# LoRa_Sensor.net
KiCad netlist of a schematic drawn in EAGLE
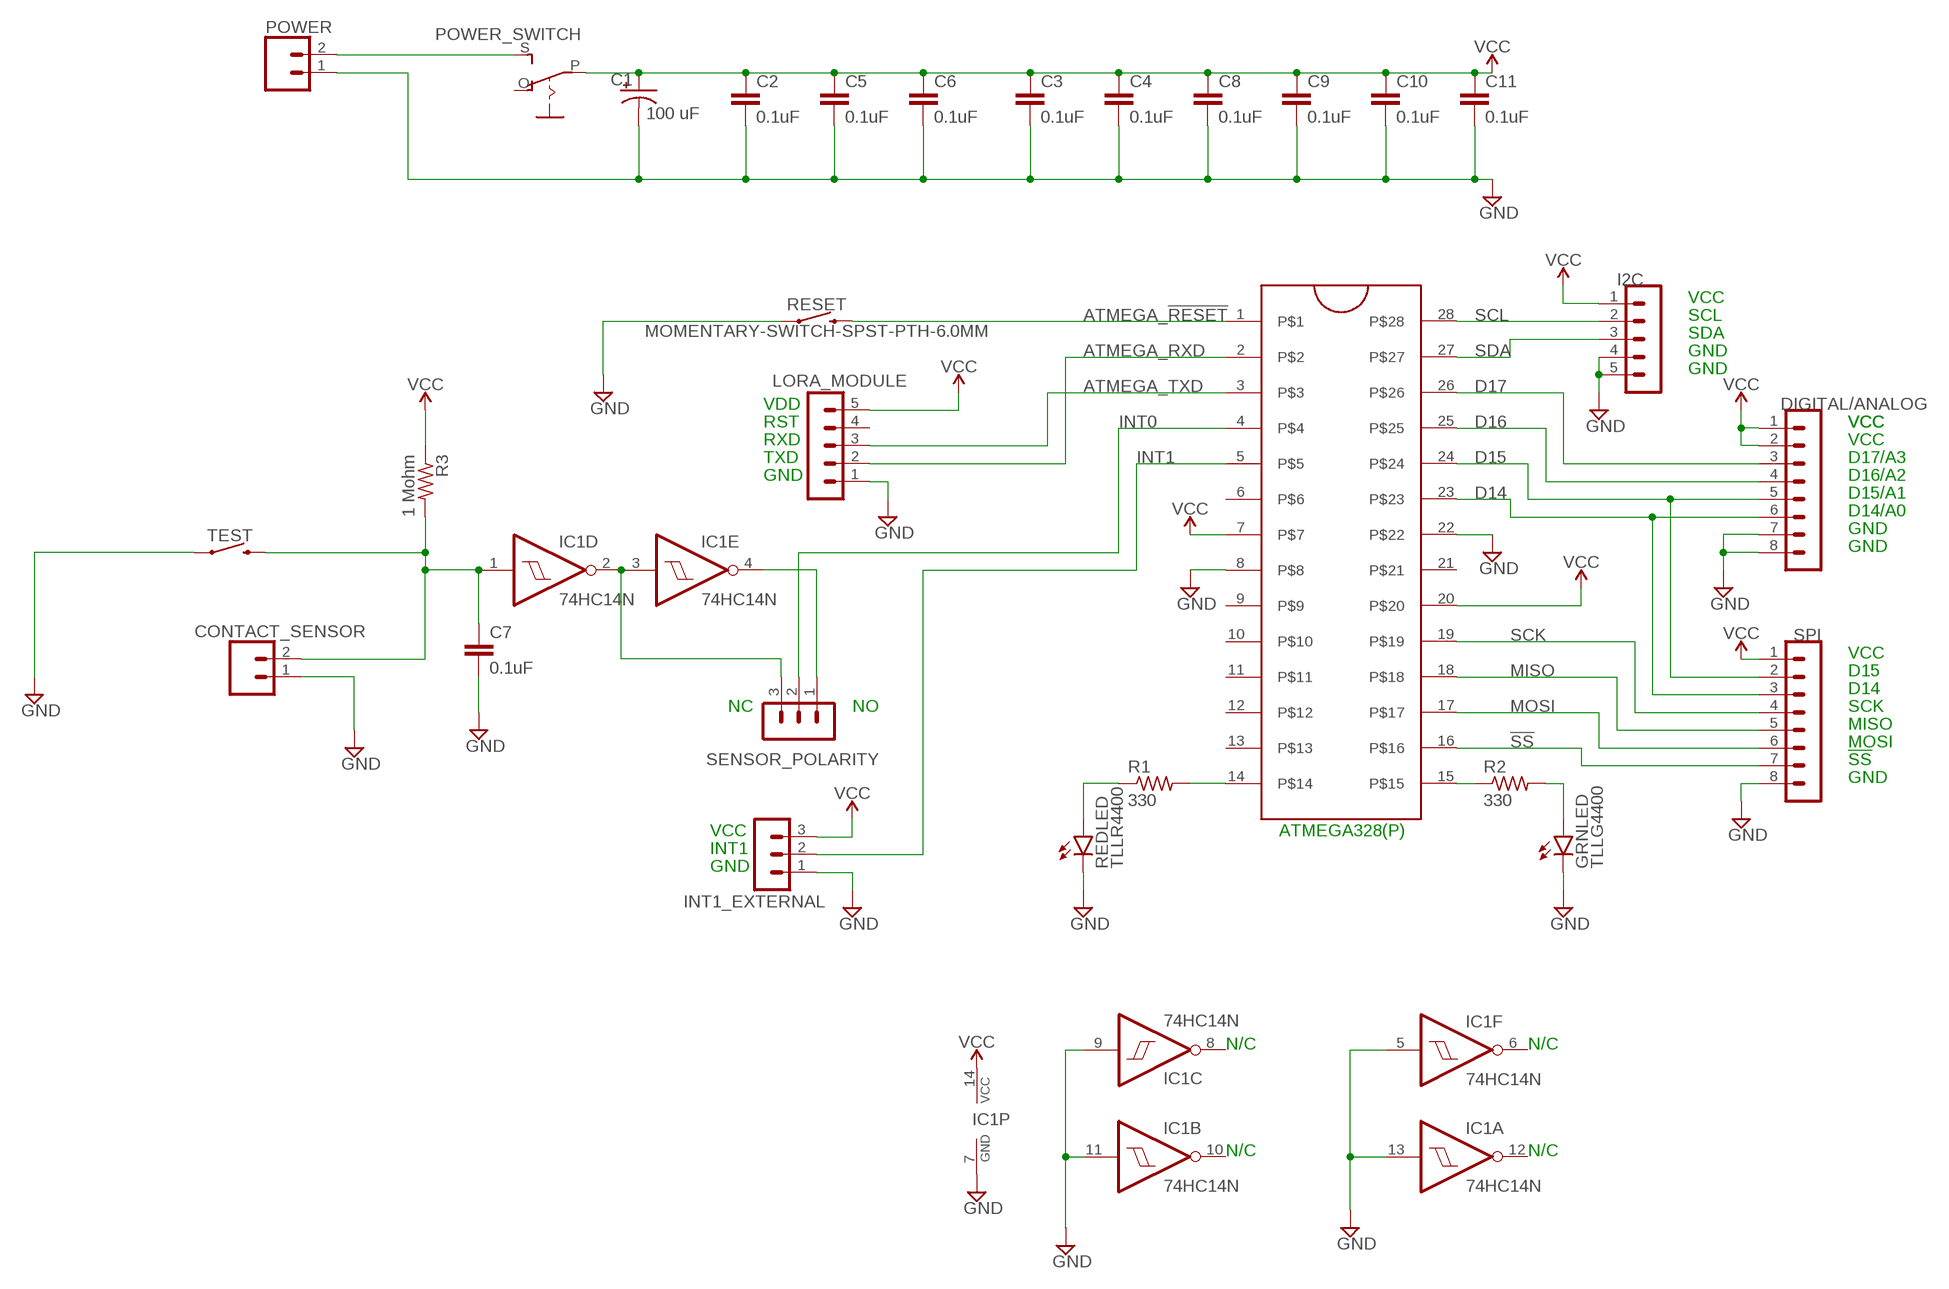
[diagram p0: schematic, sheet 1]

(export (version "E")
  (design (tool "Eeschema 10.0.6"))
  (components
    (comp (ref "C1")
      (value "100 uF")
      (footprint "eagle-import:E2,5-6")
      (libsource (lib "eagle-import") (part "CPOL-USE2.5-6"))
    )
    (comp (ref "C2")
      (value "0.1uF")
      (footprint "eagle-import:CAP-PTH-SMALL-KIT")
      (libsource (lib "eagle-import") (part "0.1UF-KIT-EZ-50V-20%"))
    )
    (comp (ref "C3")
      (value "0.1uF")
      (footprint "eagle-import:CAP-PTH-SMALL-KIT")
      (libsource (lib "eagle-import") (part "0.1UF-KIT-EZ-50V-20%"))
    )
    (comp (ref "C4")
      (value "0.1uF")
      (footprint "eagle-import:CAP-PTH-SMALL-KIT")
      (libsource (lib "eagle-import") (part "0.1UF-KIT-EZ-50V-20%"))
    )
    (comp (ref "C5")
      (value "0.1uF")
      (footprint "eagle-import:CAP-PTH-SMALL-KIT")
      (libsource (lib "eagle-import") (part "0.1UF-KIT-EZ-50V-20%"))
    )
    (comp (ref "C6")
      (value "0.1uF")
      (footprint "eagle-import:CAP-PTH-SMALL-KIT")
      (libsource (lib "eagle-import") (part "0.1UF-KIT-EZ-50V-20%"))
    )
    (comp (ref "C7")
      (value "0.1uF")
      (footprint "eagle-import:CAP-PTH-SMALL-KIT")
      (libsource (lib "eagle-import") (part "0.1UF-KIT-EZ-50V-20%"))
    )
    (comp (ref "C8")
      (value "0.1uF")
      (footprint "eagle-import:CAP-PTH-SMALL-KIT")
      (libsource (lib "eagle-import") (part "0.1UF-KIT-EZ-50V-20%"))
    )
    (comp (ref "C9")
      (value "0.1uF")
      (footprint "eagle-import:CAP-PTH-SMALL-KIT")
      (libsource (lib "eagle-import") (part "0.1UF-KIT-EZ-50V-20%"))
    )
    (comp (ref "C10")
      (value "0.1uF")
      (footprint "eagle-import:CAP-PTH-SMALL-KIT")
      (libsource (lib "eagle-import") (part "0.1UF-KIT-EZ-50V-20%"))
    )
    (comp (ref "C11")
      (value "0.1uF")
      (footprint "eagle-import:CAP-PTH-SMALL-KIT")
      (libsource (lib "eagle-import") (part "0.1UF-KIT-EZ-50V-20%"))
    )
    (comp (ref "CONTACT_SENSOR")
      (value "CONN_023.5MM")
      (footprint "eagle-import:SCREWTERMINAL-3.5MM-2")
      (libsource (lib "eagle-import") (part "CONN_023.5MM"))
    )
    (comp (ref "DIGITAL/ANALOG")
      (value "MA08-1")
      (footprint "eagle-import:MA08-1")
      (libsource (lib "eagle-import") (part "MA08-1"))
    )
    (comp (ref "GRNLED")
      (value "TLLG4400")
      (footprint "eagle-import:LED3MM")
      (fields (field (name "MF") "VISHAY SEMICONDUCTOR"))
      (libsource (lib "eagle-import") (part "TLLG4400"))
    )
    (comp (ref "I2C")
      (value "MA05-1")
      (footprint "eagle-import:MA05-1")
      (libsource (lib "eagle-import") (part "MA05-1"))
    )
    (comp (ref "IC1")
      (value "74HC14N")
      (footprint "eagle-import:DIL14")
      (libsource (lib "eagle-import") (part "7414NHC"))
    )
    (comp (ref "INT1_EXTERNAL")
      (value "MA03-1")
      (footprint "eagle-import:MA03-1")
      (libsource (lib "eagle-import") (part "MA03-1"))
    )
    (comp (ref "J1")
      (value "ZIFSOCKET-28-3\"")
      (footprint "eagle-import:DIL28-3-ZIF_SOCKET")
      (libsource (lib "eagle-import") (part "ZIFSOCKET-28-3{dblquote}"))
    )
    (comp (ref "LORA_MODULE")
      (value "MA05-1")
      (footprint "eagle-import:MA05-1")
      (libsource (lib "eagle-import") (part "MA05-1"))
    )
    (comp (ref "POWER")
      (value "CONN_023.5MM")
      (footprint "eagle-import:SCREWTERMINAL-3.5MM-2")
      (libsource (lib "eagle-import") (part "CONN_023.5MM"))
    )
    (comp (ref "POWER_SWITCH")
      (value "EG1218S")
      (footprint "eagle-import:EG1218")
      (libsource (lib "eagle-import") (part "EG1218S"))
    )
    (comp (ref "R1")
      (value "330")
      (footprint "eagle-import:0309_12")
      (libsource (lib "eagle-import") (part "R-US_0309/12"))
    )
    (comp (ref "R2")
      (value "330")
      (footprint "eagle-import:0309_12")
      (libsource (lib "eagle-import") (part "R-US_0309/12"))
    )
    (comp (ref "R3")
      (value "1 Mohm")
      (footprint "eagle-import:0309_12")
      (libsource (lib "eagle-import") (part "R-US_0309/12"))
    )
    (comp (ref "REDLED")
      (value "TLLR4400")
      (footprint "eagle-import:LED3MM")
      (fields (field (name "MF") "VISHAY SEMICONDUCTOR"))
      (libsource (lib "eagle-import") (part "TLLR4400"))
    )
    (comp (ref "RESET")
      (value "MOMENTARY-SWITCH-SPST-PTH-6.0MM")
      (footprint "eagle-import:TACTILE_SWITCH_PTH_6.0MM")
      (libsource (lib "eagle-import") (part "MOMENTARY-SWITCH-SPST-PTH-6.0MM"))
    )
    (comp (ref "SENSOR_POLARITY")
      (value "MA03-1")
      (footprint "eagle-import:MA03-1")
      (libsource (lib "eagle-import") (part "MA03-1"))
    )
    (comp (ref "SPI")
      (value "MA08-1")
      (footprint "eagle-import:MA08-1")
      (libsource (lib "eagle-import") (part "MA08-1"))
    )
    (comp (ref "TEST")
      (value "MOMENTARY-SWITCH-SPST-PTH-6.0MM")
      (footprint "eagle-import:TACTILE_SWITCH_PTH_6.0MM")
      (libsource (lib "eagle-import") (part "MOMENTARY-SWITCH-SPST-PTH-6.0MM"))
    )
  )
  (nets
    (net (code "1") (name "/ATMEGA_RXD") (class "Default")
      (node (ref "J1") (pin "2") (pinfunction "P$2_2") (pintype "bidirectional"))
      (node (ref "LORA_MODULE") (pin "2") (pinfunction "2_2") (pintype "passive"))
    )
    (net (code "2") (name "/ATMEGA_TXD") (class "Default")
      (node (ref "J1") (pin "3") (pinfunction "P$3_3") (pintype "bidirectional"))
      (node (ref "LORA_MODULE") (pin "3") (pinfunction "3_3") (pintype "passive"))
    )
    (net (code "3") (name "/ATMEGA_~{RESET}") (class "Default")
      (node (ref "J1") (pin "1") (pinfunction "P$1_1") (pintype "bidirectional"))
      (node (ref "RESET") (pin "3") (pinfunction "2_3") (pintype "passive"))
    )
    (net (code "4") (name "/D14") (class "Default")
      (node (ref "DIGITAL/ANALOG") (pin "6") (pinfunction "6_6") (pintype "passive"))
      (node (ref "J1") (pin "23") (pinfunction "P$23_23") (pintype "bidirectional"))
      (node (ref "SPI") (pin "3") (pinfunction "3_3") (pintype "passive"))
    )
    (net (code "5") (name "/D15") (class "Default")
      (node (ref "DIGITAL/ANALOG") (pin "5") (pinfunction "5_5") (pintype "passive"))
      (node (ref "J1") (pin "24") (pinfunction "P$24_24") (pintype "bidirectional"))
      (node (ref "SPI") (pin "2") (pinfunction "2_2") (pintype "passive"))
    )
    (net (code "6") (name "/D16") (class "Default")
      (node (ref "DIGITAL/ANALOG") (pin "4") (pinfunction "4_4") (pintype "passive"))
      (node (ref "J1") (pin "25") (pinfunction "P$25_25") (pintype "bidirectional"))
    )
    (net (code "7") (name "/D17") (class "Default")
      (node (ref "DIGITAL/ANALOG") (pin "3") (pinfunction "3_3") (pintype "passive"))
      (node (ref "J1") (pin "26") (pinfunction "P$26_26") (pintype "bidirectional"))
    )
    (net (code "8") (name "/INT0") (class "Default")
      (node (ref "J1") (pin "4") (pinfunction "P$4_4") (pintype "bidirectional"))
      (node (ref "SENSOR_POLARITY") (pin "2") (pinfunction "2_2") (pintype "passive"))
    )
    (net (code "9") (name "/INT1") (class "Default")
      (node (ref "INT1_EXTERNAL") (pin "2") (pinfunction "2_2") (pintype "passive"))
      (node (ref "J1") (pin "5") (pinfunction "P$5_5") (pintype "bidirectional"))
    )
    (net (code "10") (name "/MISO") (class "Default")
      (node (ref "J1") (pin "18") (pinfunction "P$18_18") (pintype "bidirectional"))
      (node (ref "SPI") (pin "5") (pinfunction "5_5") (pintype "passive"))
    )
    (net (code "11") (name "/MOSI") (class "Default")
      (node (ref "J1") (pin "17") (pinfunction "P$17_17") (pintype "bidirectional"))
      (node (ref "SPI") (pin "6") (pinfunction "6_6") (pintype "passive"))
    )
    (net (code "12") (name "/SCK") (class "Default")
      (node (ref "J1") (pin "19") (pinfunction "P$19_19") (pintype "bidirectional"))
      (node (ref "SPI") (pin "4") (pinfunction "4_4") (pintype "passive"))
    )
    (net (code "13") (name "/SCL") (class "Default")
      (node (ref "I2C") (pin "2") (pinfunction "2_2") (pintype "passive"))
      (node (ref "J1") (pin "28") (pinfunction "P$28_28") (pintype "bidirectional"))
    )
    (net (code "14") (name "/SDA") (class "Default")
      (node (ref "I2C") (pin "3") (pinfunction "3_3") (pintype "passive"))
      (node (ref "J1") (pin "27") (pinfunction "P$27_27") (pintype "bidirectional"))
    )
    (net (code "15") (name "/~{SS}") (class "Default")
      (node (ref "J1") (pin "16") (pinfunction "P$16_16") (pintype "bidirectional"))
      (node (ref "SPI") (pin "7") (pinfunction "7_7") (pintype "passive"))
    )
    (net (code "16") (name "GND") (class "Default")
      (node (ref "C1") (pin "-") (pinfunction "-_-") (pintype "passive"))
      (node (ref "C10") (pin "2") (pinfunction "2_2") (pintype "passive"))
      (node (ref "C11") (pin "2") (pinfunction "2_2") (pintype "passive"))
      (node (ref "C2") (pin "2") (pinfunction "2_2") (pintype "passive"))
      (node (ref "C3") (pin "2") (pinfunction "2_2") (pintype "passive"))
      (node (ref "C4") (pin "2") (pinfunction "2_2") (pintype "passive"))
      (node (ref "C5") (pin "2") (pinfunction "2_2") (pintype "passive"))
      (node (ref "C6") (pin "2") (pinfunction "2_2") (pintype "passive"))
      (node (ref "C7") (pin "2") (pinfunction "2_2") (pintype "passive"))
      (node (ref "C8") (pin "2") (pinfunction "2_2") (pintype "passive"))
      (node (ref "C9") (pin "2") (pinfunction "2_2") (pintype "passive"))
      (node (ref "CONTACT_SENSOR") (pin "1") (pinfunction "1_1") (pintype "passive"))
      (node (ref "DIGITAL/ANALOG") (pin "7") (pinfunction "7_7") (pintype "passive"))
      (node (ref "DIGITAL/ANALOG") (pin "8") (pinfunction "8_8") (pintype "passive"))
      (node (ref "GRNLED") (pin "K") (pinfunction "C_K") (pintype "passive"))
      (node (ref "I2C") (pin "4") (pinfunction "4_4") (pintype "passive"))
      (node (ref "I2C") (pin "5") (pinfunction "5_5") (pintype "passive"))
      (node (ref "IC1") (pin "11") (pinfunction "I_11") (pintype "input"))
      (node (ref "IC1") (pin "13") (pinfunction "I_13") (pintype "input"))
      (node (ref "IC1") (pin "5") (pinfunction "I_5") (pintype "input"))
      (node (ref "IC1") (pin "7") (pinfunction "GND_7") (pintype "power_in"))
      (node (ref "IC1") (pin "9") (pinfunction "I_9") (pintype "input"))
      (node (ref "INT1_EXTERNAL") (pin "1") (pinfunction "1_1") (pintype "passive"))
      (node (ref "J1") (pin "22") (pinfunction "P$22_22") (pintype "bidirectional"))
      (node (ref "J1") (pin "8") (pinfunction "P$8_8") (pintype "bidirectional"))
      (node (ref "LORA_MODULE") (pin "1") (pinfunction "1_1") (pintype "passive"))
      (node (ref "POWER") (pin "1") (pinfunction "1_1") (pintype "passive"))
      (node (ref "REDLED") (pin "K") (pinfunction "C_K") (pintype "passive"))
      (node (ref "RESET") (pin "1") (pinfunction "1_1") (pintype "passive"))
      (node (ref "SPI") (pin "8") (pinfunction "8_8") (pintype "passive"))
      (node (ref "TEST") (pin "1") (pinfunction "1_1") (pintype "passive"))
    )
    (net (code "17") (name "Net-(GRNLED-PadA)") (class "Default")
      (node (ref "GRNLED") (pin "A") (pinfunction "A_A") (pintype "passive"))
      (node (ref "R2") (pin "2") (pinfunction "2_2") (pintype "passive"))
    )
    (net (code "18") (name "Net-(IC1D-I)") (class "Default")
      (node (ref "C7") (pin "1") (pinfunction "1_1") (pintype "passive"))
      (node (ref "CONTACT_SENSOR") (pin "2") (pinfunction "2_2") (pintype "passive"))
      (node (ref "IC1") (pin "1") (pinfunction "I_1") (pintype "input"))
      (node (ref "R3") (pin "2") (pinfunction "2_2") (pintype "passive"))
      (node (ref "TEST") (pin "3") (pinfunction "2_3") (pintype "passive"))
    )
    (net (code "19") (name "Net-(IC1D-O)") (class "Default")
      (node (ref "IC1") (pin "2") (pinfunction "O_2") (pintype "output"))
      (node (ref "IC1") (pin "3") (pinfunction "I_3") (pintype "input"))
      (node (ref "SENSOR_POLARITY") (pin "3") (pinfunction "3_3") (pintype "passive"))
    )
    (net (code "20") (name "Net-(IC1E-O)") (class "Default")
      (node (ref "IC1") (pin "4") (pinfunction "O_4") (pintype "output"))
      (node (ref "SENSOR_POLARITY") (pin "1") (pinfunction "1_1") (pintype "passive"))
    )
    (net (code "21") (name "Net-(J1-P$14)") (class "Default")
      (node (ref "J1") (pin "14") (pinfunction "P$14_14") (pintype "bidirectional"))
      (node (ref "R1") (pin "2") (pinfunction "2_2") (pintype "passive"))
    )
    (net (code "22") (name "Net-(J1-P$15)") (class "Default")
      (node (ref "J1") (pin "15") (pinfunction "P$15_15") (pintype "bidirectional"))
      (node (ref "R2") (pin "1") (pinfunction "1_1") (pintype "passive"))
    )
    (net (code "23") (name "Net-(POWER-Pad2)") (class "Default")
      (node (ref "POWER") (pin "2") (pinfunction "2_2") (pintype "passive"))
      (node (ref "POWER_SWITCH") (pin "S") (pinfunction "S_S") (pintype "passive"))
    )
    (net (code "24") (name "Net-(R1-Pad1)") (class "Default")
      (node (ref "R1") (pin "1") (pinfunction "1_1") (pintype "passive"))
      (node (ref "REDLED") (pin "A") (pinfunction "A_A") (pintype "passive"))
    )
    (net (code "25") (name "VCC") (class "Default")
      (node (ref "C1") (pin "+") (pinfunction "+_+") (pintype "passive"))
      (node (ref "C10") (pin "1") (pinfunction "1_1") (pintype "passive"))
      (node (ref "C11") (pin "1") (pinfunction "1_1") (pintype "passive"))
      (node (ref "C2") (pin "1") (pinfunction "1_1") (pintype "passive"))
      (node (ref "C3") (pin "1") (pinfunction "1_1") (pintype "passive"))
      (node (ref "C4") (pin "1") (pinfunction "1_1") (pintype "passive"))
      (node (ref "C5") (pin "1") (pinfunction "1_1") (pintype "passive"))
      (node (ref "C6") (pin "1") (pinfunction "1_1") (pintype "passive"))
      (node (ref "C8") (pin "1") (pinfunction "1_1") (pintype "passive"))
      (node (ref "C9") (pin "1") (pinfunction "1_1") (pintype "passive"))
      (node (ref "DIGITAL/ANALOG") (pin "1") (pinfunction "1_1") (pintype "passive"))
      (node (ref "DIGITAL/ANALOG") (pin "2") (pinfunction "2_2") (pintype "passive"))
      (node (ref "I2C") (pin "1") (pinfunction "1_1") (pintype "passive"))
      (node (ref "IC1") (pin "14") (pinfunction "VCC_14") (pintype "power_in"))
      (node (ref "INT1_EXTERNAL") (pin "3") (pinfunction "3_3") (pintype "passive"))
      (node (ref "J1") (pin "20") (pinfunction "P$20_20") (pintype "bidirectional"))
      (node (ref "J1") (pin "7") (pinfunction "P$7_7") (pintype "bidirectional"))
      (node (ref "LORA_MODULE") (pin "5") (pinfunction "5_5") (pintype "passive"))
      (node (ref "POWER_SWITCH") (pin "P") (pinfunction "P_P") (pintype "passive"))
      (node (ref "R3") (pin "1") (pinfunction "1_1") (pintype "passive"))
      (node (ref "SPI") (pin "1") (pinfunction "1_1") (pintype "passive"))
    )
    (net (code "26") (name "unconnected-(IC1A-O-Pad12)") (class "Default")
      (node (ref "IC1") (pin "12") (pinfunction "O_12") (pintype "output"))
    )
    (net (code "27") (name "unconnected-(IC1B-O-Pad10)") (class "Default")
      (node (ref "IC1") (pin "10") (pinfunction "O_10") (pintype "output"))
    )
    (net (code "28") (name "unconnected-(IC1C-O-Pad8)") (class "Default")
      (node (ref "IC1") (pin "8") (pinfunction "O_8") (pintype "output"))
    )
    (net (code "29") (name "unconnected-(IC1F-O-Pad6)") (class "Default")
      (node (ref "IC1") (pin "6") (pinfunction "O_6") (pintype "output"))
    )
    (net (code "30") (name "unconnected-(J1-P$6-Pad6)") (class "Default")
      (node (ref "J1") (pin "6") (pinfunction "P$6_6") (pintype "bidirectional"))
    )
    (net (code "31") (name "unconnected-(J1-P$9-Pad9)") (class "Default")
      (node (ref "J1") (pin "9") (pinfunction "P$9_9") (pintype "bidirectional"))
    )
    (net (code "32") (name "unconnected-(J1-P$10-Pad10)") (class "Default")
      (node (ref "J1") (pin "10") (pinfunction "P$10_10") (pintype "bidirectional"))
    )
    (net (code "33") (name "unconnected-(J1-P$11-Pad11)") (class "Default")
      (node (ref "J1") (pin "11") (pinfunction "P$11_11") (pintype "bidirectional"))
    )
    (net (code "34") (name "unconnected-(J1-P$12-Pad12)") (class "Default")
      (node (ref "J1") (pin "12") (pinfunction "P$12_12") (pintype "bidirectional"))
    )
    (net (code "35") (name "unconnected-(J1-P$13-Pad13)") (class "Default")
      (node (ref "J1") (pin "13") (pinfunction "P$13_13") (pintype "bidirectional"))
    )
    (net (code "36") (name "unconnected-(J1-P$21-Pad21)") (class "Default")
      (node (ref "J1") (pin "21") (pinfunction "P$21_21") (pintype "bidirectional"))
    )
    (net (code "37") (name "unconnected-(LORA_MODULE-Pad4)") (class "Default")
      (node (ref "LORA_MODULE") (pin "4") (pinfunction "4_4") (pintype "passive"))
    )
    (net (code "38") (name "unconnected-(POWER_SWITCH-PadO)") (class "Default")
      (node (ref "POWER_SWITCH") (pin "O") (pinfunction "O_O") (pintype "passive"))
    )
  )
)
